# SCH.net
KiCad netlist of a schematic drawn in Altium Designer
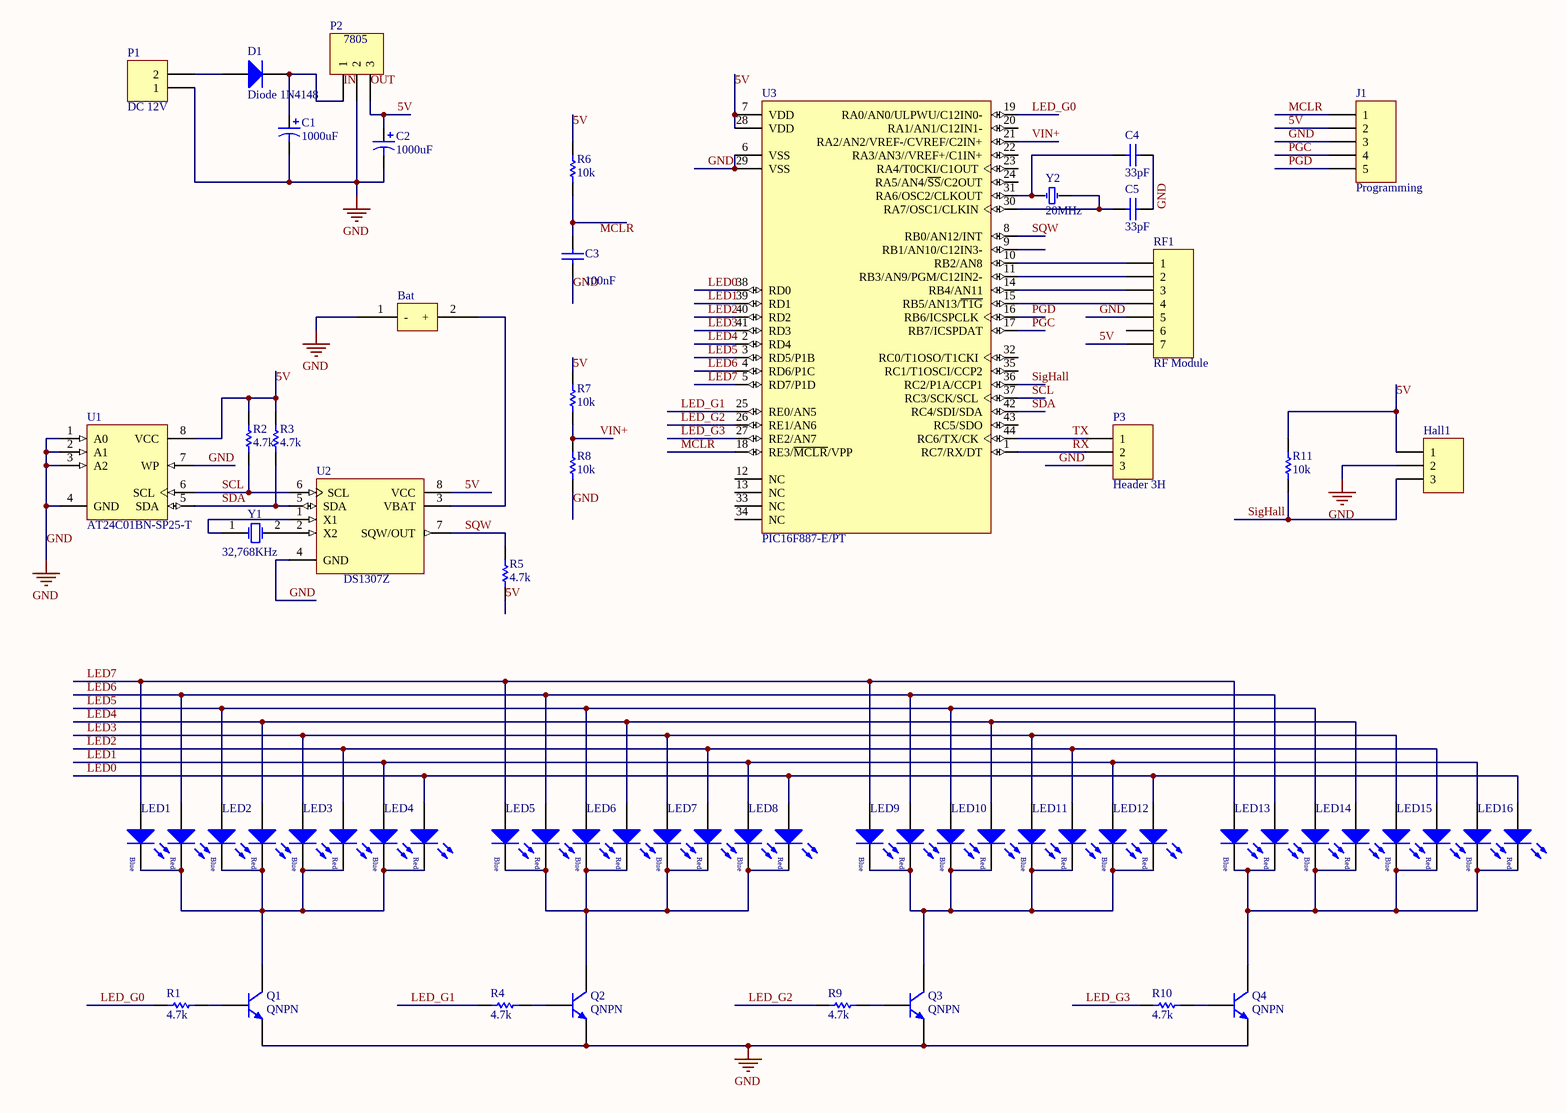
[diagram p0: SCH.SchDoc]

(export (version "E")
  (design (tool "Eeschema 10.0.6"))
  (components
    (comp (ref "Bat") (value "Battery") (footprint "BATTERY") (libsource (lib "Battery") (part "Battery")))
    (comp (ref "C1")
      (value "1000uF")
      (footprint "CAP POL 2")
      (description "Polarized Capacitor (Surface Mount)")
      (fields (field (name "Comment") "Cap Pol3") (field (name "PUBLISHER") "Altium Limited"))
      (libsource (lib "Miscellaneous Devices") (part "Cap Pol3"))
    )
    (comp (ref "C2")
      (value "1000uF")
      (footprint "CAP POL 2")
      (description "Polarized Capacitor (Surface Mount)")
      (fields (field (name "Comment") "Cap Pol3") (field (name "PUBLISHER") "Altium Limited"))
      (libsource (lib "Miscellaneous Devices") (part "Cap Pol3"))
    )
    (comp (ref "C3")
      (value "100nF")
      (footprint "SM/C_0805")
      (description "Capacitor (Semiconductor SIM Model)")
      (fields (field (name "Comment") "Cap Semi") (field (name "PUBLISHER") "Altium Limited"))
      (libsource (lib "Miscellaneous Devices") (part "Cap Semi"))
    )
    (comp (ref "C4")
      (value "33pF")
      (footprint "SM/C_0805")
      (description "Capacitor (Semiconductor SIM Model)")
      (fields (field (name "Comment") "Cap Semi") (field (name "PUBLISHER") "Altium Limited"))
      (libsource (lib "Miscellaneous Devices") (part "Cap Semi"))
    )
    (comp (ref "C5")
      (value "33pF")
      (footprint "SM/C_0805")
      (description "Capacitor (Semiconductor SIM Model)")
      (fields (field (name "Comment") "Cap Semi") (field (name "PUBLISHER") "Altium Limited"))
      (libsource (lib "Miscellaneous Devices") (part "Cap Semi"))
    )
    (comp (ref "D1")
      (value "Diode 1N4148")
      (footprint "DO-35")
      (description "High Conductance Fast Diode")
      (fields (field (name "PUBLISHER") "Altium Limited"))
      (libsource (lib "Miscellaneous Devices") (part "Diode 1N4148"))
    )
    (comp (ref "Hall1")
      (value "Header 3")
      (footprint "HDR1X3")
      (description "Header, 3-Pin")
      (fields (field (name "PUBLISHER") "Altium Limited"))
      (libsource (lib "Miscellaneous Connectors") (part "Header 3"))
    )
    (comp (ref "J1")
      (value "Programming")
      (footprint "HDR1X5H")
      (description "Header, 5-Pin, Right Angle")
      (fields (field (name "PUBLISHER") "Altium Limited"))
      (libsource (lib "Miscellaneous Connectors") (part "Header 5H"))
    )
    (comp (ref "LED1")
      (value "150141RB73100")
      (footprint "3528")
      (description "SMD Bi-Color Top LED, WL-SBTW, Red & Blue")
      (fields
        (field (name "MANUFACTURER") "Würth Elektronik eiSos GmbH")
        (field (name "CREATED BY") "Christin Otto")
      )
      (libsource (lib "Altium_WE_eiSos_WL-SBTW") (part "WL-SBTW 3528 150141RB73100"))
    )
    (comp (ref "LED2")
      (value "150141RB73100")
      (footprint "3528")
      (description "SMD Bi-Color Top LED, WL-SBTW, Red & Blue")
      (fields
        (field (name "MANUFACTURER") "Würth Elektronik eiSos GmbH")
        (field (name "CREATED BY") "Christin Otto")
      )
      (libsource (lib "Altium_WE_eiSos_WL-SBTW") (part "WL-SBTW 3528 150141RB73100"))
    )
    (comp (ref "LED3")
      (value "150141RB73100")
      (footprint "3528")
      (description "SMD Bi-Color Top LED, WL-SBTW, Red & Blue")
      (fields
        (field (name "MANUFACTURER") "Würth Elektronik eiSos GmbH")
        (field (name "CREATED BY") "Christin Otto")
      )
      (libsource (lib "Altium_WE_eiSos_WL-SBTW") (part "WL-SBTW 3528 150141RB73100"))
    )
    (comp (ref "LED4")
      (value "150141RB73100")
      (footprint "3528")
      (description "SMD Bi-Color Top LED, WL-SBTW, Red & Blue")
      (fields
        (field (name "MANUFACTURER") "Würth Elektronik eiSos GmbH")
        (field (name "CREATED BY") "Christin Otto")
      )
      (libsource (lib "Altium_WE_eiSos_WL-SBTW") (part "WL-SBTW 3528 150141RB73100"))
    )
    (comp (ref "LED5")
      (value "150141RB73100")
      (footprint "3528")
      (description "SMD Bi-Color Top LED, WL-SBTW, Red & Blue")
      (fields
        (field (name "MANUFACTURER") "Würth Elektronik eiSos GmbH")
        (field (name "CREATED BY") "Christin Otto")
      )
      (libsource (lib "Altium_WE_eiSos_WL-SBTW") (part "WL-SBTW 3528 150141RB73100"))
    )
    (comp (ref "LED6")
      (value "150141RB73100")
      (footprint "3528")
      (description "SMD Bi-Color Top LED, WL-SBTW, Red & Blue")
      (fields
        (field (name "MANUFACTURER") "Würth Elektronik eiSos GmbH")
        (field (name "CREATED BY") "Christin Otto")
      )
      (libsource (lib "Altium_WE_eiSos_WL-SBTW") (part "WL-SBTW 3528 150141RB73100"))
    )
    (comp (ref "LED7")
      (value "150141RB73100")
      (footprint "3528")
      (description "SMD Bi-Color Top LED, WL-SBTW, Red & Blue")
      (fields
        (field (name "MANUFACTURER") "Würth Elektronik eiSos GmbH")
        (field (name "CREATED BY") "Christin Otto")
      )
      (libsource (lib "Altium_WE_eiSos_WL-SBTW") (part "WL-SBTW 3528 150141RB73100"))
    )
    (comp (ref "LED8")
      (value "150141RB73100")
      (footprint "3528")
      (description "SMD Bi-Color Top LED, WL-SBTW, Red & Blue")
      (fields
        (field (name "MANUFACTURER") "Würth Elektronik eiSos GmbH")
        (field (name "CREATED BY") "Christin Otto")
      )
      (libsource (lib "Altium_WE_eiSos_WL-SBTW") (part "WL-SBTW 3528 150141RB73100"))
    )
    (comp (ref "LED9")
      (value "150141RB73100")
      (footprint "3528")
      (description "SMD Bi-Color Top LED, WL-SBTW, Red & Blue")
      (fields
        (field (name "MANUFACTURER") "Würth Elektronik eiSos GmbH")
        (field (name "CREATED BY") "Christin Otto")
      )
      (libsource (lib "Altium_WE_eiSos_WL-SBTW") (part "WL-SBTW 3528 150141RB73100"))
    )
    (comp (ref "LED10")
      (value "150141RB73100")
      (footprint "3528")
      (description "SMD Bi-Color Top LED, WL-SBTW, Red & Blue")
      (fields
        (field (name "MANUFACTURER") "Würth Elektronik eiSos GmbH")
        (field (name "CREATED BY") "Christin Otto")
      )
      (libsource (lib "Altium_WE_eiSos_WL-SBTW") (part "WL-SBTW 3528 150141RB73100"))
    )
    (comp (ref "LED11")
      (value "150141RB73100")
      (footprint "3528")
      (description "SMD Bi-Color Top LED, WL-SBTW, Red & Blue")
      (fields
        (field (name "MANUFACTURER") "Würth Elektronik eiSos GmbH")
        (field (name "CREATED BY") "Christin Otto")
      )
      (libsource (lib "Altium_WE_eiSos_WL-SBTW") (part "WL-SBTW 3528 150141RB73100"))
    )
    (comp (ref "LED12")
      (value "150141RB73100")
      (footprint "3528")
      (description "SMD Bi-Color Top LED, WL-SBTW, Red & Blue")
      (fields
        (field (name "MANUFACTURER") "Würth Elektronik eiSos GmbH")
        (field (name "CREATED BY") "Christin Otto")
      )
      (libsource (lib "Altium_WE_eiSos_WL-SBTW") (part "WL-SBTW 3528 150141RB73100"))
    )
    (comp (ref "LED13")
      (value "150141RB73100")
      (footprint "3528")
      (description "SMD Bi-Color Top LED, WL-SBTW, Red & Blue")
      (fields
        (field (name "MANUFACTURER") "Würth Elektronik eiSos GmbH")
        (field (name "CREATED BY") "Christin Otto")
      )
      (libsource (lib "Altium_WE_eiSos_WL-SBTW") (part "WL-SBTW 3528 150141RB73100"))
    )
    (comp (ref "LED14")
      (value "150141RB73100")
      (footprint "3528")
      (description "SMD Bi-Color Top LED, WL-SBTW, Red & Blue")
      (fields
        (field (name "MANUFACTURER") "Würth Elektronik eiSos GmbH")
        (field (name "CREATED BY") "Christin Otto")
      )
      (libsource (lib "Altium_WE_eiSos_WL-SBTW") (part "WL-SBTW 3528 150141RB73100"))
    )
    (comp (ref "LED15")
      (value "150141RB73100")
      (footprint "3528")
      (description "SMD Bi-Color Top LED, WL-SBTW, Red & Blue")
      (fields
        (field (name "MANUFACTURER") "Würth Elektronik eiSos GmbH")
        (field (name "CREATED BY") "Christin Otto")
      )
      (libsource (lib "Altium_WE_eiSos_WL-SBTW") (part "WL-SBTW 3528 150141RB73100"))
    )
    (comp (ref "LED16")
      (value "150141RB73100")
      (footprint "3528")
      (description "SMD Bi-Color Top LED, WL-SBTW, Red & Blue")
      (fields
        (field (name "MANUFACTURER") "Würth Elektronik eiSos GmbH")
        (field (name "CREATED BY") "Christin Otto")
      )
      (libsource (lib "Altium_WE_eiSos_WL-SBTW") (part "WL-SBTW 3528 150141RB73100"))
    )
    (comp (ref "P1")
      (value "DC 12V")
      (footprint "HDR1X2H")
      (description "Header, 2-Pin, Right Angle")
      (fields (field (name "PUBLISHER") "Altium Limited"))
      (libsource (lib "Miscellaneous Connectors") (part "Header 2H"))
    )
    (comp (ref "P2")
      (value "7805")
      (footprint "HDR1X3")
      (description "Header, 3-Pin")
      (fields (field (name "PUBLISHER") "Altium Limited"))
      (libsource (lib "") (part "Header 3_1"))
    )
    (comp (ref "P3")
      (value "Header 3H")
      (footprint "HDR1X3H")
      (description "Header, 3-Pin, Right Angle")
      (fields (field (name "PUBLISHER") "Altium Limited"))
      (libsource (lib "Miscellaneous Connectors") (part "Header 3H"))
    )
    (comp (ref "Q1")
      (value "QNPN")
      (footprint "SOT-23B_N")
      (description "NPN Bipolar Transistor")
      (fields (field (name "PUBLISHER") "Altium Limited"))
      (libsource (lib "Miscellaneous Devices") (part "QNPN"))
    )
    (comp (ref "Q2")
      (value "QNPN")
      (footprint "SOT-23B_N")
      (description "NPN Bipolar Transistor")
      (fields (field (name "PUBLISHER") "Altium Limited"))
      (libsource (lib "Miscellaneous Devices") (part "QNPN"))
    )
    (comp (ref "Q3")
      (value "QNPN")
      (footprint "SOT-23B_N")
      (description "NPN Bipolar Transistor")
      (fields (field (name "PUBLISHER") "Altium Limited"))
      (libsource (lib "Miscellaneous Devices") (part "QNPN"))
    )
    (comp (ref "Q4")
      (value "QNPN")
      (footprint "SOT-23B_N")
      (description "NPN Bipolar Transistor")
      (fields (field (name "PUBLISHER") "Altium Limited"))
      (libsource (lib "Miscellaneous Devices") (part "QNPN"))
    )
    (comp (ref "R1")
      (value "4.7k")
      (footprint "SM/C_0805")
      (description "Semiconductor Resistor")
      (fields (field (name "Comment") "Res Semi") (field (name "PUBLISHER") "Altium Limited"))
      (libsource (lib "Miscellaneous Devices") (part "Res Semi"))
    )
    (comp (ref "R2")
      (value "4.7k")
      (footprint "SM/C_0805")
      (description "Semiconductor Resistor")
      (fields (field (name "Comment") "Res Semi") (field (name "PUBLISHER") "Altium Limited"))
      (libsource (lib "Miscellaneous Devices") (part "Res Semi"))
    )
    (comp (ref "R3")
      (value "4.7k")
      (footprint "SM/C_0805")
      (description "Semiconductor Resistor")
      (fields (field (name "Comment") "Res Semi") (field (name "PUBLISHER") "Altium Limited"))
      (libsource (lib "Miscellaneous Devices") (part "Res Semi"))
    )
    (comp (ref "R4")
      (value "4.7k")
      (footprint "SM/C_0805")
      (description "Semiconductor Resistor")
      (fields (field (name "Comment") "Res Semi") (field (name "PUBLISHER") "Altium Limited"))
      (libsource (lib "Miscellaneous Devices") (part "Res Semi"))
    )
    (comp (ref "R5")
      (value "4.7k")
      (footprint "SM/C_0805")
      (description "Semiconductor Resistor")
      (fields (field (name "Comment") "Res Semi") (field (name "PUBLISHER") "Altium Limited"))
      (libsource (lib "Miscellaneous Devices") (part "Res Semi"))
    )
    (comp (ref "R6")
      (value "10k")
      (footprint "SM/C_0805")
      (description "Semiconductor Resistor")
      (fields (field (name "Comment") "Res Semi") (field (name "PUBLISHER") "Altium Limited"))
      (libsource (lib "Miscellaneous Devices") (part "Res Semi"))
    )
    (comp (ref "R7")
      (value "10k")
      (footprint "SM/C_0805")
      (description "Semiconductor Resistor")
      (fields (field (name "Comment") "Res Semi") (field (name "PUBLISHER") "Altium Limited"))
      (libsource (lib "Miscellaneous Devices") (part "Res Semi"))
    )
    (comp (ref "R8")
      (value "10k")
      (footprint "SM/C_0805")
      (description "Semiconductor Resistor")
      (fields (field (name "Comment") "Res Semi") (field (name "PUBLISHER") "Altium Limited"))
      (libsource (lib "Miscellaneous Devices") (part "Res Semi"))
    )
    (comp (ref "R9")
      (value "4.7k")
      (footprint "SM/C_0805")
      (description "Semiconductor Resistor")
      (fields (field (name "Comment") "Res Semi") (field (name "PUBLISHER") "Altium Limited"))
      (libsource (lib "Miscellaneous Devices") (part "Res Semi"))
    )
    (comp (ref "R10")
      (value "4.7k")
      (footprint "SM/C_0805")
      (description "Semiconductor Resistor")
      (fields (field (name "Comment") "Res Semi") (field (name "PUBLISHER") "Altium Limited"))
      (libsource (lib "Miscellaneous Devices") (part "Res Semi"))
    )
    (comp (ref "R11")
      (value "10k")
      (footprint "SM/C_0805")
      (description "Semiconductor Resistor")
      (fields (field (name "Comment") "Res Semi") (field (name "PUBLISHER") "Altium Limited"))
      (libsource (lib "Miscellaneous Devices") (part "Res Semi"))
    )
    (comp (ref "RF1")
      (value "RF Module")
      (footprint "HDR1X7")
      (description "Header, 7-Pin")
      (fields (field (name "PUBLISHER") "Altium Limited"))
      (libsource (lib "Miscellaneous Connectors") (part "Header 7"))
    )
    (comp (ref "U1")
      (value "AT24C01BN-SP25-T")
      (footprint "8S1_N")
      (fields (field (name "PUBLISHER") "Altium Limited"))
      (libsource (lib "Atmel Memory Serial EEPROM") (part "AT24C01BN-SP25-T"))
    )
    (comp (ref "U2")
      (value "DS1307Z")
      (footprint "SOIC8N_N")
      (description "64 X 8 Serial Real-Time Clock")
      (fields (field (name "PUBLISHER") "Altium Limited"))
      (libsource (lib "Dallas Peripheral Real Time Clock") (part "DS1307Z"))
    )
    (comp (ref "U3")
      (value "PIC16F887-E/PT")
      (footprint "TQFP-PT44_N")
      (fields (field (name "PUBLISHER") "Altium Limited"))
      (libsource (lib "Microchip Microcontroller 8-Bit PIC16") (part "PIC16F887-E/PT"))
    )
    (comp (ref "Y1")
      (value "32,768KHz")
      (footprint "CFPX-93")
      (description "Surface Mount Quartz Crystal")
      (fields (field (name "PUBLISHER") "Altium Limited"))
      (libsource (lib "C-MAC Crystal Oscillator") (part "CFPX-93"))
    )
    (comp (ref "Y2") (value "20MHz") (footprint "CRYSTAL") (libsource (lib "FUFO") (part "XTAL")))
  )
  (nets
    (net (code "1") (name "/5V") (class "Default")
      (node (ref "C2") (pin "1") (pinfunction "1_1") (pintype "passive"))
      (node (ref "Hall1") (pin "1") (pinfunction "1_1") (pintype "passive"))
      (node (ref "J1") (pin "2") (pinfunction "2_2") (pintype "passive"))
      (node (ref "P2") (pin "3") (pinfunction "3_3") (pintype "passive"))
      (node (ref "R11") (pin "2") (pinfunction "2_2") (pintype "passive"))
      (node (ref "R2") (pin "2") (pinfunction "2_2") (pintype "passive"))
      (node (ref "R3") (pin "2") (pinfunction "2_2") (pintype "passive"))
      (node (ref "R5") (pin "1") (pinfunction "1_1") (pintype "passive"))
      (node (ref "R6") (pin "2") (pinfunction "2_2") (pintype "passive"))
      (node (ref "R7") (pin "2") (pinfunction "2_2") (pintype "passive"))
      (node (ref "RF1") (pin "7") (pinfunction "7_7") (pintype "passive"))
      (node (ref "U1") (pin "8") (pinfunction "VCC_8") (pintype "power_in"))
      (node (ref "U2") (pin "8") (pinfunction "VCC_8") (pintype "power_in"))
      (node (ref "U3") (pin "28") (pinfunction "VDD_28") (pintype "power_in"))
      (node (ref "U3") (pin "7") (pinfunction "VDD_7") (pintype "power_in"))
    )
    (net (code "3") (name "/LED0") (class "Default")
      (node (ref "LED12") (pin "1") (pinfunction "A_1") (pintype "passive"))
      (node (ref "LED16") (pin "1") (pinfunction "A_1") (pintype "passive"))
      (node (ref "LED4") (pin "1") (pinfunction "A_1") (pintype "passive"))
      (node (ref "LED8") (pin "1") (pinfunction "A_1") (pintype "passive"))
      (node (ref "U3") (pin "38") (pinfunction "RD0_38") (pintype "bidirectional"))
    )
    (net (code "4") (name "/LED1") (class "Default")
      (node (ref "LED12") (pin "2") (pinfunction "A_2") (pintype "passive"))
      (node (ref "LED16") (pin "2") (pinfunction "A_2") (pintype "passive"))
      (node (ref "LED4") (pin "2") (pinfunction "A_2") (pintype "passive"))
      (node (ref "LED8") (pin "2") (pinfunction "A_2") (pintype "passive"))
      (node (ref "U3") (pin "39") (pinfunction "RD1_39") (pintype "bidirectional"))
    )
    (net (code "5") (name "/LED2") (class "Default")
      (node (ref "LED11") (pin "1") (pinfunction "A_1") (pintype "passive"))
      (node (ref "LED15") (pin "1") (pinfunction "A_1") (pintype "passive"))
      (node (ref "LED3") (pin "1") (pinfunction "A_1") (pintype "passive"))
      (node (ref "LED7") (pin "1") (pinfunction "A_1") (pintype "passive"))
      (node (ref "U3") (pin "40") (pinfunction "RD2_40") (pintype "bidirectional"))
    )
    (net (code "6") (name "/LED3") (class "Default")
      (node (ref "LED11") (pin "2") (pinfunction "A_2") (pintype "passive"))
      (node (ref "LED15") (pin "2") (pinfunction "A_2") (pintype "passive"))
      (node (ref "LED3") (pin "2") (pinfunction "A_2") (pintype "passive"))
      (node (ref "LED7") (pin "2") (pinfunction "A_2") (pintype "passive"))
      (node (ref "U3") (pin "41") (pinfunction "RD3_41") (pintype "bidirectional"))
    )
    (net (code "7") (name "/LED4") (class "Default")
      (node (ref "LED10") (pin "1") (pinfunction "A_1") (pintype "passive"))
      (node (ref "LED14") (pin "1") (pinfunction "A_1") (pintype "passive"))
      (node (ref "LED2") (pin "1") (pinfunction "A_1") (pintype "passive"))
      (node (ref "LED6") (pin "1") (pinfunction "A_1") (pintype "passive"))
      (node (ref "U3") (pin "2") (pinfunction "RD4_2") (pintype "bidirectional"))
    )
    (net (code "8") (name "/LED5") (class "Default")
      (node (ref "LED10") (pin "2") (pinfunction "A_2") (pintype "passive"))
      (node (ref "LED14") (pin "2") (pinfunction "A_2") (pintype "passive"))
      (node (ref "LED2") (pin "2") (pinfunction "A_2") (pintype "passive"))
      (node (ref "LED6") (pin "2") (pinfunction "A_2") (pintype "passive"))
      (node (ref "U3") (pin "3") (pinfunction "RD5/P1B_3") (pintype "bidirectional"))
    )
    (net (code "9") (name "/LED6") (class "Default")
      (node (ref "LED1") (pin "1") (pinfunction "A_1") (pintype "passive"))
      (node (ref "LED13") (pin "1") (pinfunction "A_1") (pintype "passive"))
      (node (ref "LED5") (pin "1") (pinfunction "A_1") (pintype "passive"))
      (node (ref "LED9") (pin "1") (pinfunction "A_1") (pintype "passive"))
      (node (ref "U3") (pin "4") (pinfunction "RD6/P1C_4") (pintype "bidirectional"))
    )
    (net (code "10") (name "/LED7") (class "Default")
      (node (ref "LED1") (pin "2") (pinfunction "A_2") (pintype "passive"))
      (node (ref "LED13") (pin "2") (pinfunction "A_2") (pintype "passive"))
      (node (ref "LED5") (pin "2") (pinfunction "A_2") (pintype "passive"))
      (node (ref "LED9") (pin "2") (pinfunction "A_2") (pintype "passive"))
      (node (ref "U3") (pin "5") (pinfunction "RD7/P1D_5") (pintype "bidirectional"))
    )
    (net (code "11") (name "/LED_G0") (class "Default")
      (node (ref "R1") (pin "2") (pinfunction "2_2") (pintype "passive"))
      (node (ref "U3") (pin "19") (pinfunction "RA0/AN0/ULPWU/C12IN0-_19") (pintype "bidirectional"))
    )
    (net (code "12") (name "/LED_G1") (class "Default")
      (node (ref "R4") (pin "2") (pinfunction "2_2") (pintype "passive"))
      (node (ref "U3") (pin "25") (pinfunction "RE0/AN5_25") (pintype "bidirectional"))
    )
    (net (code "13") (name "/LED_G2") (class "Default")
      (node (ref "R9") (pin "2") (pinfunction "2_2") (pintype "passive"))
      (node (ref "U3") (pin "26") (pinfunction "RE1/AN6_26") (pintype "bidirectional"))
    )
    (net (code "14") (name "/LED_G3") (class "Default")
      (node (ref "R10") (pin "2") (pinfunction "2_2") (pintype "passive"))
      (node (ref "U3") (pin "27") (pinfunction "RE2/AN7_27") (pintype "bidirectional"))
    )
    (net (code "15") (name "/MCLR") (class "Default")
      (node (ref "J1") (pin "1") (pinfunction "1_1") (pintype "passive"))
      (node (ref "U3") (pin "18") (pinfunction "RE3/~{MCLR}/VPP_18") (pintype "bidirectional"))
    )
    (net (code "17") (name "/PGC") (class "Default")
      (node (ref "J1") (pin "4") (pinfunction "4_4") (pintype "passive"))
      (node (ref "U3") (pin "17") (pinfunction "RB7/ICSPDAT_17") (pintype "bidirectional"))
    )
    (net (code "18") (name "/PGD") (class "Default")
      (node (ref "J1") (pin "5") (pinfunction "5_5") (pintype "passive"))
      (node (ref "U3") (pin "16") (pinfunction "RB6/ICSPCLK_16") (pintype "bidirectional"))
    )
    (net (code "19") (name "/RX") (class "Default")
      (node (ref "P3") (pin "2") (pinfunction "2_2") (pintype "passive"))
      (node (ref "U3") (pin "1") (pinfunction "RC7/RX/DT_1") (pintype "bidirectional"))
    )
    (net (code "20") (name "/SCL") (class "Default")
      (node (ref "R2") (pin "1") (pinfunction "1_1") (pintype "passive"))
      (node (ref "U1") (pin "6") (pinfunction "SCL_6") (pintype "input"))
      (node (ref "U2") (pin "6") (pinfunction "SCL_6") (pintype "input"))
      (node (ref "U3") (pin "37") (pinfunction "RC3/SCK/SCL_37") (pintype "bidirectional"))
    )
    (net (code "21") (name "/SDA") (class "Default")
      (node (ref "R3") (pin "1") (pinfunction "1_1") (pintype "passive"))
      (node (ref "U1") (pin "5") (pinfunction "SDA_5") (pintype "bidirectional"))
      (node (ref "U2") (pin "5") (pinfunction "SDA_5") (pintype "bidirectional"))
      (node (ref "U3") (pin "42") (pinfunction "RC4/SDI/SDA_42") (pintype "bidirectional"))
    )
    (net (code "22") (name "/SQW") (class "Default")
      (node (ref "R5") (pin "2") (pinfunction "2_2") (pintype "passive"))
      (node (ref "U2") (pin "7") (pinfunction "SQW/OUT_7") (pintype "output"))
      (node (ref "U3") (pin "8") (pinfunction "RB0/AN12/INT_8") (pintype "bidirectional"))
    )
    (net (code "23") (name "/SigHall") (class "Default")
      (node (ref "Hall1") (pin "3") (pinfunction "3_3") (pintype "passive"))
      (node (ref "R11") (pin "1") (pinfunction "1_1") (pintype "passive"))
      (node (ref "U3") (pin "36") (pinfunction "RC2/P1A/CCP1_36") (pintype "bidirectional"))
    )
    (net (code "24") (name "/TX") (class "Default")
      (node (ref "P3") (pin "1") (pinfunction "1_1") (pintype "passive"))
      (node (ref "U3") (pin "44") (pinfunction "RC6/TX/CK_44") (pintype "bidirectional"))
    )
    (net (code "25") (name "/VIN+") (class "Default")
      (node (ref "R7") (pin "1") (pinfunction "1_1") (pintype "passive"))
      (node (ref "R8") (pin "2") (pinfunction "2_2") (pintype "passive"))
      (node (ref "U3") (pin "21") (pinfunction "RA2/AN2/VREF-/CVREF/C2IN+_21") (pintype "bidirectional"))
    )
    (net (code "26") (name "GND") (class "Default")
      (node (ref "Bat") (pin "1") (pinfunction "-_1") (pintype "passive"))
      (node (ref "C1") (pin "2") (pinfunction "2_2") (pintype "passive"))
      (node (ref "C2") (pin "2") (pinfunction "2_2") (pintype "passive"))
      (node (ref "C3") (pin "1") (pinfunction "1_1") (pintype "passive"))
      (node (ref "C4") (pin "1") (pinfunction "1_1") (pintype "passive"))
      (node (ref "C5") (pin "1") (pinfunction "1_1") (pintype "passive"))
      (node (ref "Hall1") (pin "2") (pinfunction "2_2") (pintype "passive"))
      (node (ref "J1") (pin "3") (pinfunction "3_3") (pintype "passive"))
      (node (ref "P1") (pin "1") (pinfunction "1_1") (pintype "passive"))
      (node (ref "P2") (pin "2") (pinfunction "2_2") (pintype "passive"))
      (node (ref "P3") (pin "3") (pinfunction "3_3") (pintype "passive"))
      (node (ref "Q1") (pin "3") (pinfunction "E_3") (pintype "passive"))
      (node (ref "Q2") (pin "3") (pinfunction "E_3") (pintype "passive"))
      (node (ref "Q3") (pin "3") (pinfunction "E_3") (pintype "passive"))
      (node (ref "Q4") (pin "3") (pinfunction "E_3") (pintype "passive"))
      (node (ref "R8") (pin "1") (pinfunction "1_1") (pintype "passive"))
      (node (ref "RF1") (pin "5") (pinfunction "5_5") (pintype "passive"))
      (node (ref "U1") (pin "1") (pinfunction "A0_1") (pintype "input"))
      (node (ref "U1") (pin "2") (pinfunction "A1_2") (pintype "input"))
      (node (ref "U1") (pin "3") (pinfunction "A2_3") (pintype "input"))
      (node (ref "U1") (pin "4") (pinfunction "GND_4") (pintype "power_in"))
      (node (ref "U1") (pin "7") (pinfunction "WP_7") (pintype "input"))
      (node (ref "U2") (pin "4") (pinfunction "GND_4") (pintype "power_in"))
      (node (ref "U3") (pin "29") (pinfunction "VSS_29") (pintype "power_in"))
      (node (ref "U3") (pin "6") (pinfunction "VSS_6") (pintype "power_in"))
    )
    (net (code "27") (name "Net-(Bat-+)") (class "Default")
      (node (ref "Bat") (pin "2") (pinfunction "+_2") (pintype "passive"))
      (node (ref "U2") (pin "3") (pinfunction "VBAT_3") (pintype "power_in"))
    )
    (net (code "28") (name "Net-(C3-Pad2)") (class "Default")
      (node (ref "C3") (pin "2") (pinfunction "2_2") (pintype "passive"))
      (node (ref "R6") (pin "1") (pinfunction "1_1") (pintype "passive"))
    )
    (net (code "29") (name "Net-(D1-A)") (class "Default")
      (node (ref "D1") (pin "1") (pinfunction "A_1") (pintype "passive"))
      (node (ref "P1") (pin "2") (pinfunction "2_2") (pintype "passive"))
    )
    (net (code "30") (name "Net-(D1-K)") (class "Default")
      (node (ref "C1") (pin "1") (pinfunction "1_1") (pintype "passive"))
      (node (ref "D1") (pin "2") (pinfunction "K_2") (pintype "passive"))
      (node (ref "P2") (pin "1") (pinfunction "1_1") (pintype "passive"))
    )
    (net (code "31") (name "Net-(Q1-B)") (class "Default")
      (node (ref "Q1") (pin "2") (pinfunction "B_2") (pintype "passive"))
      (node (ref "R1") (pin "1") (pinfunction "1_1") (pintype "passive"))
    )
    (net (code "32") (name "Net-(Q1-C)") (class "Default")
      (node (ref "LED1") (pin "3") (pinfunction "C_3") (pintype "passive"))
      (node (ref "LED1") (pin "4") (pinfunction "C_4") (pintype "passive"))
      (node (ref "LED2") (pin "3") (pinfunction "C_3") (pintype "passive"))
      (node (ref "LED2") (pin "4") (pinfunction "C_4") (pintype "passive"))
      (node (ref "LED3") (pin "3") (pinfunction "C_3") (pintype "passive"))
      (node (ref "LED3") (pin "4") (pinfunction "C_4") (pintype "passive"))
      (node (ref "LED4") (pin "3") (pinfunction "C_3") (pintype "passive"))
      (node (ref "LED4") (pin "4") (pinfunction "C_4") (pintype "passive"))
      (node (ref "Q1") (pin "1") (pinfunction "C_1") (pintype "passive"))
    )
    (net (code "33") (name "Net-(Q2-B)") (class "Default")
      (node (ref "Q2") (pin "2") (pinfunction "B_2") (pintype "passive"))
      (node (ref "R4") (pin "1") (pinfunction "1_1") (pintype "passive"))
    )
    (net (code "34") (name "Net-(Q2-C)") (class "Default")
      (node (ref "LED5") (pin "3") (pinfunction "C_3") (pintype "passive"))
      (node (ref "LED5") (pin "4") (pinfunction "C_4") (pintype "passive"))
      (node (ref "LED6") (pin "3") (pinfunction "C_3") (pintype "passive"))
      (node (ref "LED6") (pin "4") (pinfunction "C_4") (pintype "passive"))
      (node (ref "LED7") (pin "3") (pinfunction "C_3") (pintype "passive"))
      (node (ref "LED7") (pin "4") (pinfunction "C_4") (pintype "passive"))
      (node (ref "LED8") (pin "3") (pinfunction "C_3") (pintype "passive"))
      (node (ref "LED8") (pin "4") (pinfunction "C_4") (pintype "passive"))
      (node (ref "Q2") (pin "1") (pinfunction "C_1") (pintype "passive"))
    )
    (net (code "35") (name "Net-(Q3-B)") (class "Default")
      (node (ref "Q3") (pin "2") (pinfunction "B_2") (pintype "passive"))
      (node (ref "R9") (pin "1") (pinfunction "1_1") (pintype "passive"))
    )
    (net (code "36") (name "Net-(Q3-C)") (class "Default")
      (node (ref "LED10") (pin "3") (pinfunction "C_3") (pintype "passive"))
      (node (ref "LED10") (pin "4") (pinfunction "C_4") (pintype "passive"))
      (node (ref "LED11") (pin "3") (pinfunction "C_3") (pintype "passive"))
      (node (ref "LED11") (pin "4") (pinfunction "C_4") (pintype "passive"))
      (node (ref "LED12") (pin "3") (pinfunction "C_3") (pintype "passive"))
      (node (ref "LED12") (pin "4") (pinfunction "C_4") (pintype "passive"))
      (node (ref "LED9") (pin "3") (pinfunction "C_3") (pintype "passive"))
      (node (ref "LED9") (pin "4") (pinfunction "C_4") (pintype "passive"))
      (node (ref "Q3") (pin "1") (pinfunction "C_1") (pintype "passive"))
    )
    (net (code "37") (name "Net-(Q4-B)") (class "Default")
      (node (ref "Q4") (pin "2") (pinfunction "B_2") (pintype "passive"))
      (node (ref "R10") (pin "1") (pinfunction "1_1") (pintype "passive"))
    )
    (net (code "38") (name "Net-(Q4-C)") (class "Default")
      (node (ref "LED13") (pin "3") (pinfunction "C_3") (pintype "passive"))
      (node (ref "LED13") (pin "4") (pinfunction "C_4") (pintype "passive"))
      (node (ref "LED14") (pin "3") (pinfunction "C_3") (pintype "passive"))
      (node (ref "LED14") (pin "4") (pinfunction "C_4") (pintype "passive"))
      (node (ref "LED15") (pin "3") (pinfunction "C_3") (pintype "passive"))
      (node (ref "LED15") (pin "4") (pinfunction "C_4") (pintype "passive"))
      (node (ref "LED16") (pin "3") (pinfunction "C_3") (pintype "passive"))
      (node (ref "LED16") (pin "4") (pinfunction "C_4") (pintype "passive"))
      (node (ref "Q4") (pin "1") (pinfunction "C_1") (pintype "passive"))
    )
    (net (code "39") (name "Net-(U2-X1)") (class "Default")
      (node (ref "U2") (pin "1") (pinfunction "X1_1") (pintype "input"))
      (node (ref "Y1") (pin "1") (pinfunction "OSC1_1") (pintype "passive"))
    )
    (net (code "40") (name "Net-(U2-X2)") (class "Default")
      (node (ref "U2") (pin "2") (pinfunction "X2_2") (pintype "input"))
      (node (ref "Y1") (pin "2") (pinfunction "OSC2_2") (pintype "passive"))
    )
    (net (code "41") (name "Net-(U3-RA6{slash}OSC2{slash}CLKOUT)") (class "Default")
      (node (ref "C4") (pin "2") (pinfunction "2_2") (pintype "passive"))
      (node (ref "U3") (pin "31") (pinfunction "RA6/OSC2/CLKOUT_31") (pintype "bidirectional"))
      (node (ref "Y2") (pin "1") (pinfunction "1_1") (pintype "passive"))
    )
    (net (code "42") (name "Net-(U3-RA7{slash}OSC1{slash}CLKIN)") (class "Default")
      (node (ref "C5") (pin "2") (pinfunction "2_2") (pintype "passive"))
      (node (ref "U3") (pin "30") (pinfunction "RA7/OSC1/CLKIN_30") (pintype "bidirectional"))
      (node (ref "Y2") (pin "2") (pinfunction "2_2") (pintype "passive"))
    )
    (net (code "43") (name "Net-(U3-RB2{slash}AN8)") (class "Default")
      (node (ref "RF1") (pin "1") (pinfunction "1_1") (pintype "passive"))
      (node (ref "U3") (pin "10") (pinfunction "RB2/AN8_10") (pintype "bidirectional"))
    )
    (net (code "44") (name "Net-(U3-RB3{slash}AN9{slash}PGM{slash}C12IN2-)") (class "Default")
      (node (ref "RF1") (pin "2") (pinfunction "2_2") (pintype "passive"))
      (node (ref "U3") (pin "11") (pinfunction "RB3/AN9/PGM/C12IN2-_11") (pintype "bidirectional"))
    )
    (net (code "45") (name "Net-(U3-RB4{slash}AN11)") (class "Default")
      (node (ref "RF1") (pin "3") (pinfunction "3_3") (pintype "passive"))
      (node (ref "U3") (pin "14") (pinfunction "RB4/AN11_14") (pintype "bidirectional"))
    )
    (net (code "46") (name "Net-(U3-RB5{slash}AN13{slash}~{T1G})") (class "Default")
      (node (ref "RF1") (pin "4") (pinfunction "4_4") (pintype "passive"))
      (node (ref "U3") (pin "15") (pinfunction "RB5/AN13/~{T1G}_15") (pintype "bidirectional"))
    )
    (net (code "47") (name "unconnected-(RF1-Pad6)") (class "Default")
      (node (ref "RF1") (pin "6") (pinfunction "6_6") (pintype "passive"))
    )
    (net (code "48") (name "unconnected-(U3-NC-Pad12)") (class "Default")
      (node (ref "U3") (pin "12") (pinfunction "NC_12") (pintype "passive"))
    )
    (net (code "49") (name "unconnected-(U3-NC-Pad13)") (class "Default")
      (node (ref "U3") (pin "13") (pinfunction "NC_13") (pintype "passive"))
    )
    (net (code "50") (name "unconnected-(U3-NC-Pad33)") (class "Default")
      (node (ref "U3") (pin "33") (pinfunction "NC_33") (pintype "passive"))
    )
    (net (code "51") (name "unconnected-(U3-NC-Pad34)") (class "Default")
      (node (ref "U3") (pin "34") (pinfunction "NC_34") (pintype "passive"))
    )
    (net (code "52") (name "unconnected-(U3-RA1{slash}AN1{slash}C12IN1--Pad20)") (class "Default")
      (node (ref "U3") (pin "20") (pinfunction "RA1/AN1/C12IN1-_20") (pintype "bidirectional"))
    )
    (net (code "53") (name "unconnected-(U3-RA3{slash}AN3{slash}{slash}VREF+{slash}C1IN+-Pad22)") (class "Default")
      (node (ref "U3") (pin "22") (pinfunction "RA3/AN3//VREF+/C1IN+_22") (pintype "bidirectional"))
    )
    (net (code "54") (name "unconnected-(U3-RA4{slash}T0CKI{slash}C1OUT-Pad23)") (class "Default")
      (node (ref "U3") (pin "23") (pinfunction "RA4/T0CKI/C1OUT_23") (pintype "bidirectional"))
    )
    (net (code "55") (name "unconnected-(U3-RA5{slash}AN4{slash}~{SS}{slash}C2OUT-Pad24)") (class "Default")
      (node (ref "U3") (pin "24") (pinfunction "RA5/AN4/~{SS}/C2OUT_24") (pintype "bidirectional"))
    )
    (net (code "56") (name "unconnected-(U3-RB1{slash}AN10{slash}C12IN3--Pad9)") (class "Default")
      (node (ref "U3") (pin "9") (pinfunction "RB1/AN10/C12IN3-_9") (pintype "bidirectional"))
    )
    (net (code "57") (name "unconnected-(U3-RC0{slash}T1OSO{slash}T1CKI-Pad32)") (class "Default")
      (node (ref "U3") (pin "32") (pinfunction "RC0/T1OSO/T1CKI_32") (pintype "bidirectional"))
    )
    (net (code "58") (name "unconnected-(U3-RC1{slash}T1OSCI{slash}CCP2-Pad35)") (class "Default")
      (node (ref "U3") (pin "35") (pinfunction "RC1/T1OSCI/CCP2_35") (pintype "bidirectional"))
    )
    (net (code "59") (name "unconnected-(U3-RC5{slash}SDO-Pad43)") (class "Default")
      (node (ref "U3") (pin "43") (pinfunction "RC5/SDO_43") (pintype "bidirectional"))
    )
  )
)
